# NIRGM_V6.net
KiCad netlist of a schematic drawn in EAGLE
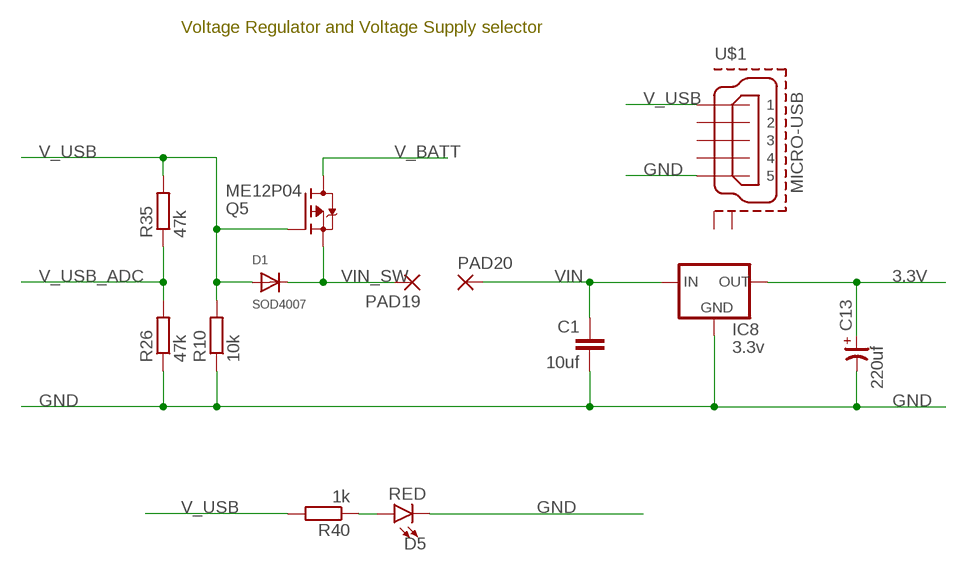
[diagram p0: schematic, sheet 1]
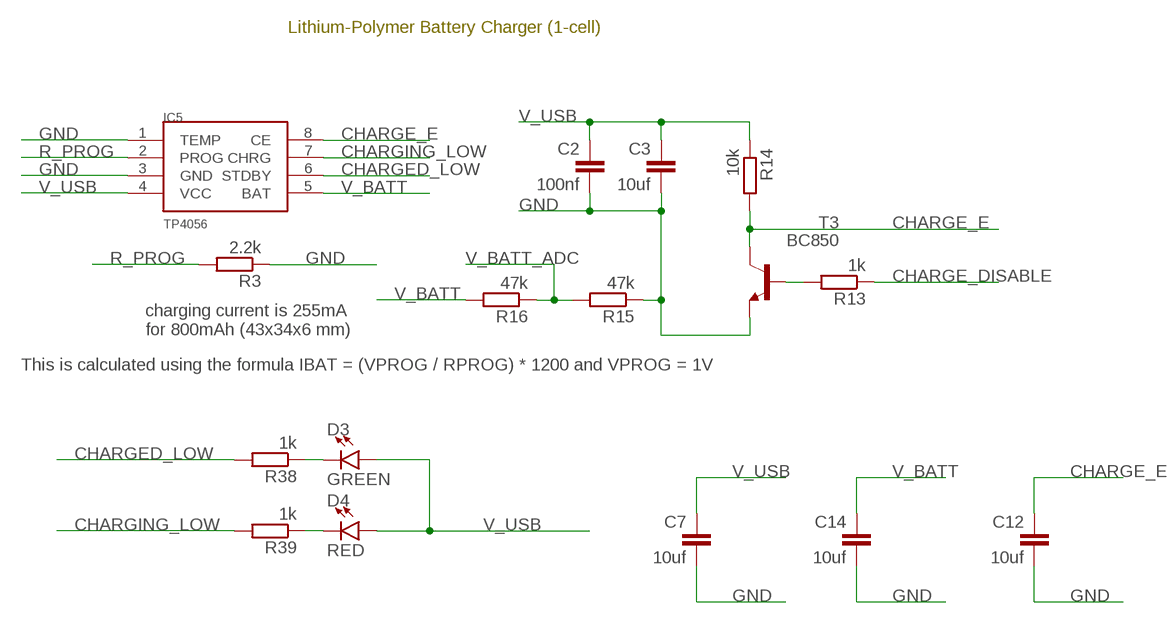
[diagram p1: schematic, sheet 2]
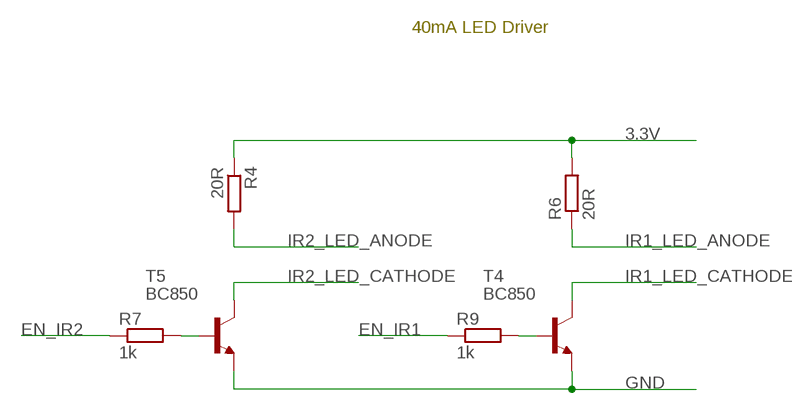
[diagram p2: schematic, sheet 3]
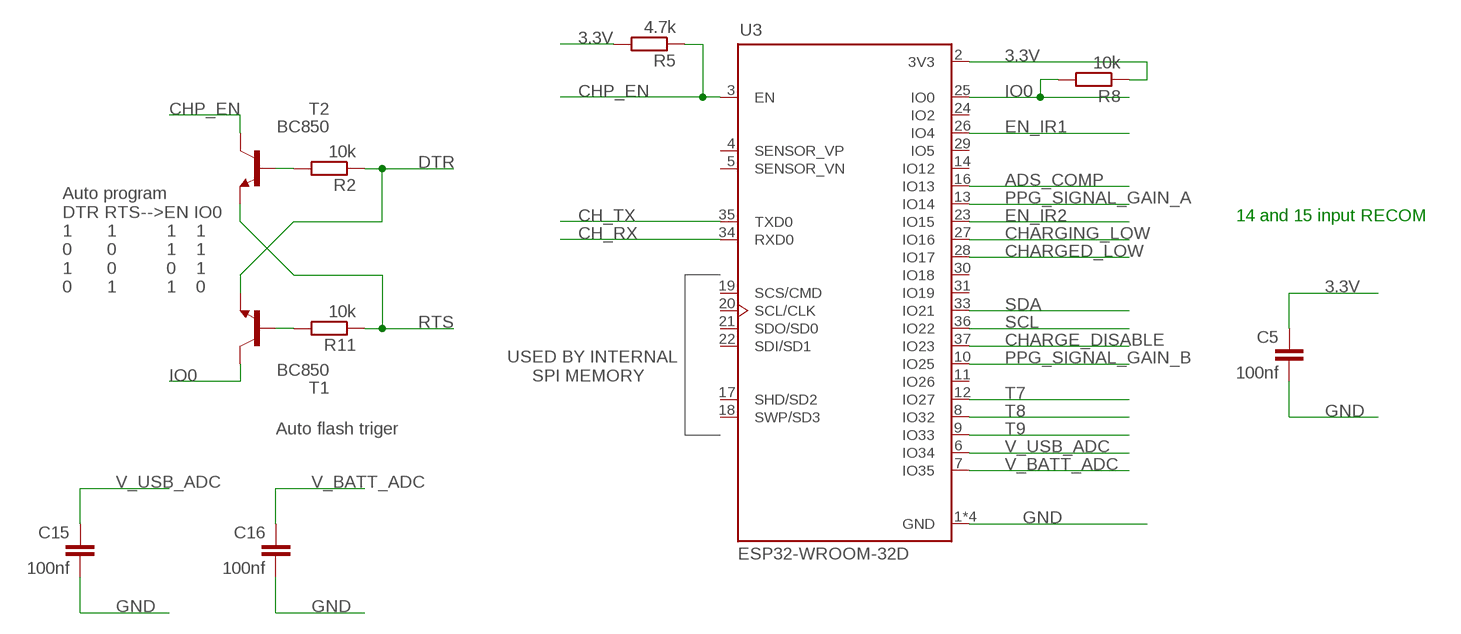
[diagram p3: schematic, sheet 4]
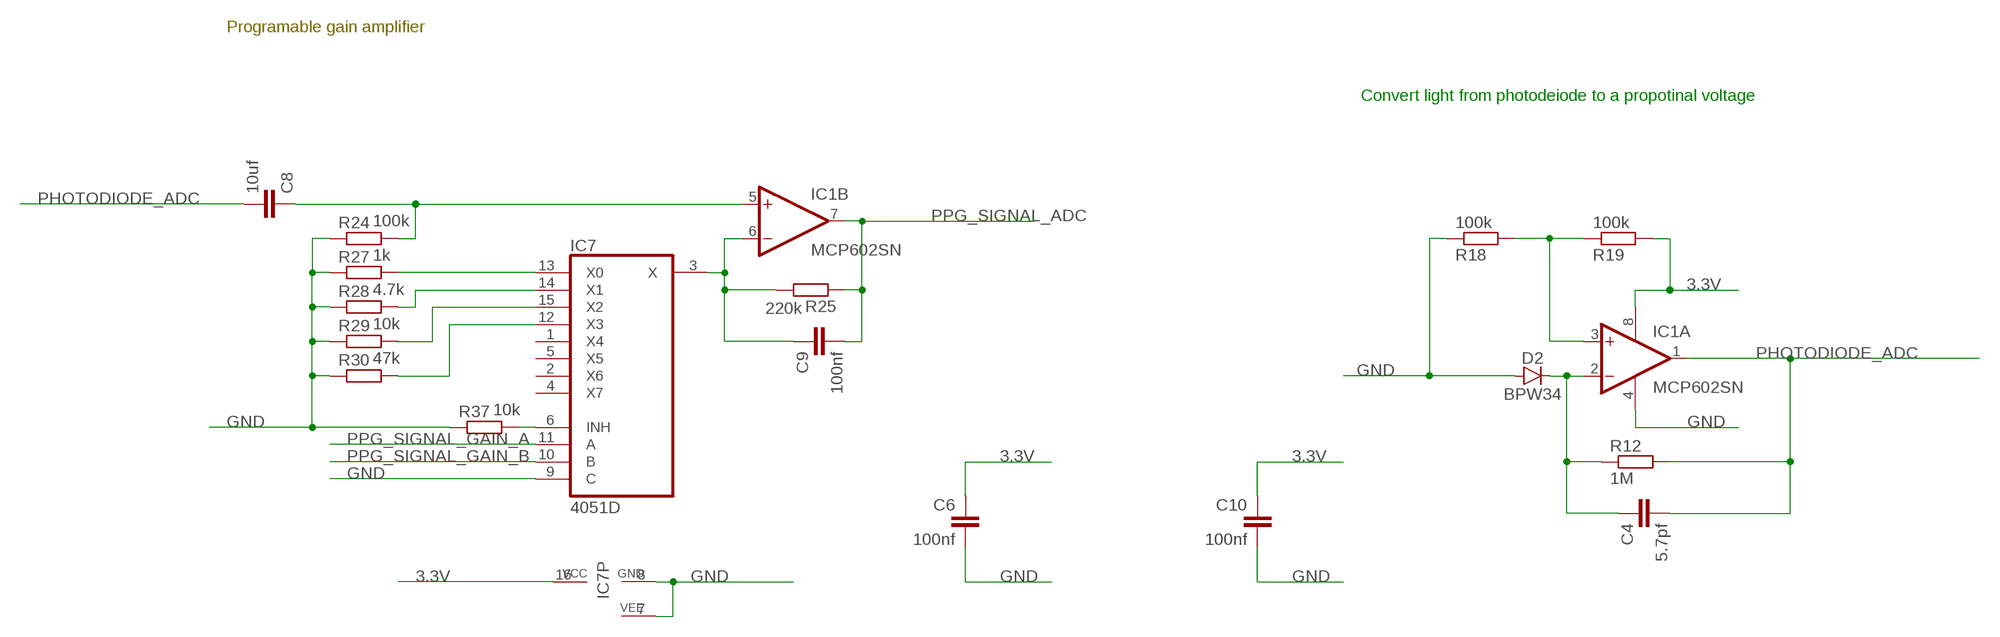
[diagram p4: schematic, sheet 5]
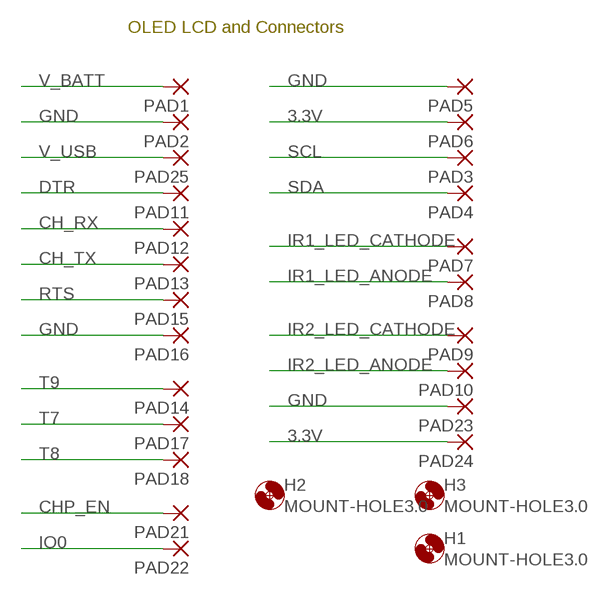
[diagram p5: schematic, sheet 6]
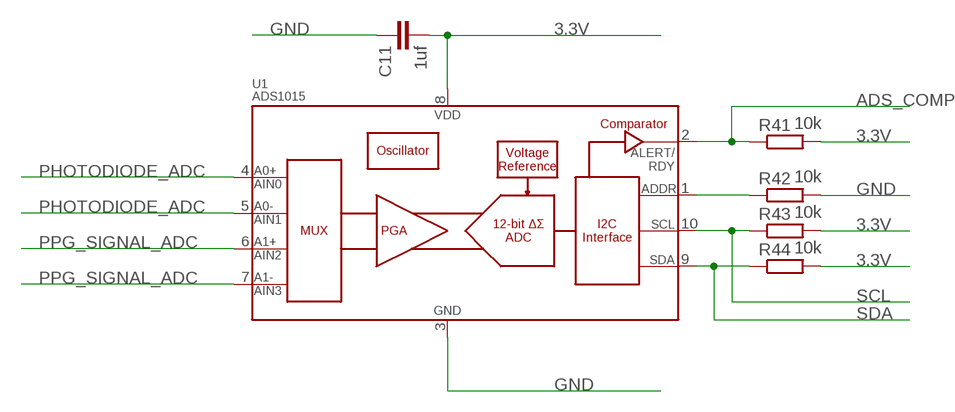
[diagram p6: schematic, sheet 7]

(export (version "E")
  (design (tool "Eeschema 10.0.6"))
  (components
    (comp (ref "C11")
      (value "1uf")
      (footprint "eagle-import:C1206K")
      (libsource (lib "eagle-import") (part "C-EUC1206K"))
    )
    (comp (ref "R41")
      (value "10k")
      (footprint "eagle-import:R1206")
      (libsource (lib "eagle-import") (part "R-EU_R1206"))
    )
    (comp (ref "R42")
      (value "10k")
      (footprint "eagle-import:R1206")
      (libsource (lib "eagle-import") (part "R-EU_R1206"))
    )
    (comp (ref "R43")
      (value "10k")
      (footprint "eagle-import:R1206")
      (libsource (lib "eagle-import") (part "R-EU_R1206"))
    )
    (comp (ref "R44")
      (value "10k")
      (footprint "eagle-import:R1206")
      (libsource (lib "eagle-import") (part "R-EU_R1206"))
    )
    (comp (ref "U1")
      (value "ADS1015")
      (footprint "eagle-import:MSOP10")
      (libsource (lib "eagle-import") (part "ADS1015"))
    )
    (comp (ref "C2")
      (value "100nf")
      (footprint "eagle-import:C1206K")
      (libsource (lib "eagle-import") (part "C-EUC1206K"))
    )
    (comp (ref "C3")
      (value "10uf")
      (footprint "eagle-import:C1206K")
      (libsource (lib "eagle-import") (part "C-EUC1206K"))
    )
    (comp (ref "C7")
      (value "10uf")
      (footprint "eagle-import:C1206K")
      (libsource (lib "eagle-import") (part "C-EUC1206K"))
    )
    (comp (ref "C12")
      (value "10uf")
      (footprint "eagle-import:C1206K")
      (libsource (lib "eagle-import") (part "C-EUC1206K"))
    )
    (comp (ref "C14")
      (value "10uf")
      (footprint "eagle-import:C1206K")
      (libsource (lib "eagle-import") (part "C-EUC1206K"))
    )
    (comp (ref "D3")
      (value "GREEN")
      (footprint "eagle-import:LED-1206")
      (libsource (lib "eagle-import") (part "LED-GREEN1206"))
    )
    (comp (ref "D4")
      (value "RED")
      (footprint "eagle-import:LED-1206")
      (libsource (lib "eagle-import") (part "LED-GREEN1206"))
    )
    (comp (ref "IC5")
      (value "TP4056")
      (footprint "eagle-import:SOP-8")
      (libsource (lib "eagle-import") (part "TP4056"))
    )
    (comp (ref "R3")
      (value "2.2k")
      (footprint "eagle-import:R1206")
      (libsource (lib "eagle-import") (part "R-EU_R1206"))
    )
    (comp (ref "R13")
      (value "1k")
      (footprint "eagle-import:R1206")
      (libsource (lib "eagle-import") (part "R-EU_R1206"))
    )
    (comp (ref "R14")
      (value "10k")
      (footprint "eagle-import:R1206")
      (libsource (lib "eagle-import") (part "R-EU_R1206"))
    )
    (comp (ref "R15")
      (value "47k")
      (footprint "eagle-import:R1206")
      (libsource (lib "eagle-import") (part "R-EU_R1206"))
    )
    (comp (ref "R16")
      (value "47k")
      (footprint "eagle-import:R1206")
      (libsource (lib "eagle-import") (part "R-EU_R1206"))
    )
    (comp (ref "R38")
      (value "1k")
      (footprint "eagle-import:R1206")
      (libsource (lib "eagle-import") (part "R-EU_R1206"))
    )
    (comp (ref "R39")
      (value "1k")
      (footprint "eagle-import:R1206")
      (libsource (lib "eagle-import") (part "R-EU_R1206"))
    )
    (comp (ref "T3")
      (value "BC850")
      (footprint "eagle-import:SOT23")
      (libsource (lib "eagle-import") (part "BC850"))
    )
    (comp (ref "C1")
      (value "10uf")
      (footprint "eagle-import:C1206K")
      (libsource (lib "eagle-import") (part "C-EUC1206K"))
    )
    (comp (ref "C13")
      (value "220uf")
      (footprint "eagle-import:7343_T")
      (libsource (lib "eagle-import") (part "CP-7343"))
    )
    (comp (ref "D1")
      (value "SOD4007")
      (footprint "eagle-import:SOD-123FL")
      (libsource (lib "eagle-import") (part "DIODE_SOD-123FL"))
    )
    (comp (ref "D5")
      (value "RED")
      (footprint "eagle-import:LED-1206")
      (libsource (lib "eagle-import") (part "LED-GREEN1206"))
    )
    (comp (ref "IC8")
      (value "3.3v")
      (footprint "eagle-import:TO252")
      (libsource (lib "eagle-import") (part "LM1117TO252"))
    )
    (comp (ref "PAD19")
      (value "SMD2")
      (footprint "eagle-import:SMD1,27-2,54")
      (libsource (lib "eagle-import") (part "SMD2"))
    )
    (comp (ref "PAD20")
      (value "SMD2")
      (footprint "eagle-import:SMD1,27-2,54")
      (libsource (lib "eagle-import") (part "SMD2"))
    )
    (comp (ref "Q5")
      (value "ME12P04")
      (footprint "eagle-import:TO252")
      (libsource (lib "eagle-import") (part "FDD4141TO252"))
    )
    (comp (ref "R10")
      (value "10k")
      (footprint "eagle-import:R1206")
      (libsource (lib "eagle-import") (part "R-EU_R1206"))
    )
    (comp (ref "R26")
      (value "47k")
      (footprint "eagle-import:R1206")
      (libsource (lib "eagle-import") (part "R-EU_R1206"))
    )
    (comp (ref "R35")
      (value "47k")
      (footprint "eagle-import:R1206")
      (libsource (lib "eagle-import") (part "R-EU_R1206"))
    )
    (comp (ref "R40")
      (value "1k")
      (footprint "eagle-import:R1206")
      (libsource (lib "eagle-import") (part "R-EU_R1206"))
    )
    (comp (ref "U$1")
      (value "MICRO-USB")
      (footprint "eagle-import:47589-0001")
      (libsource (lib "eagle-import") (part "MICRO-USB-RECEPTACLE47589-0001"))
    )
    (comp (ref "H1")
      (value "MOUNT-HOLE3.0")
      (footprint "eagle-import:3,0")
      (libsource (lib "eagle-import") (part "MOUNT-HOLE3.0"))
    )
    (comp (ref "H2")
      (value "MOUNT-HOLE3.0")
      (footprint "eagle-import:3,0")
      (libsource (lib "eagle-import") (part "MOUNT-HOLE3.0"))
    )
    (comp (ref "H3")
      (value "MOUNT-HOLE3.0")
      (footprint "eagle-import:3,0")
      (libsource (lib "eagle-import") (part "MOUNT-HOLE3.0"))
    )
    (comp (ref "PAD1")
      (value "WIREPADSMD5-2,5")
      (footprint "eagle-import:5-2,5")
      (libsource (lib "eagle-import") (part "WIREPADSMD5-2,5"))
    )
    (comp (ref "PAD2")
      (value "WIREPADSMD5-2,5")
      (footprint "eagle-import:5-2,5")
      (libsource (lib "eagle-import") (part "WIREPADSMD5-2,5"))
    )
    (comp (ref "PAD3")
      (value "SMD2")
      (footprint "eagle-import:SMD1,27-2,54")
      (libsource (lib "eagle-import") (part "SMD2"))
    )
    (comp (ref "PAD4")
      (value "SMD2")
      (footprint "eagle-import:SMD1,27-2,54")
      (libsource (lib "eagle-import") (part "SMD2"))
    )
    (comp (ref "PAD5")
      (value "SMD2")
      (footprint "eagle-import:SMD1,27-2,54")
      (libsource (lib "eagle-import") (part "SMD2"))
    )
    (comp (ref "PAD6")
      (value "SMD2")
      (footprint "eagle-import:SMD1,27-2,54")
      (libsource (lib "eagle-import") (part "SMD2"))
    )
    (comp (ref "PAD7")
      (value "SMD2")
      (footprint "eagle-import:SMD1,27-2,54")
      (libsource (lib "eagle-import") (part "SMD2"))
    )
    (comp (ref "PAD8")
      (value "SMD2")
      (footprint "eagle-import:SMD1,27-2,54")
      (libsource (lib "eagle-import") (part "SMD2"))
    )
    (comp (ref "PAD9")
      (value "SMD2")
      (footprint "eagle-import:SMD1,27-2,54")
      (libsource (lib "eagle-import") (part "SMD2"))
    )
    (comp (ref "PAD10")
      (value "SMD2")
      (footprint "eagle-import:SMD1,27-2,54")
      (libsource (lib "eagle-import") (part "SMD2"))
    )
    (comp (ref "PAD11")
      (value "SMD2")
      (footprint "eagle-import:SMD1,27-2,54")
      (libsource (lib "eagle-import") (part "SMD2"))
    )
    (comp (ref "PAD12")
      (value "SMD2")
      (footprint "eagle-import:SMD1,27-2,54")
      (libsource (lib "eagle-import") (part "SMD2"))
    )
    (comp (ref "PAD13")
      (value "SMD2")
      (footprint "eagle-import:SMD1,27-2,54")
      (libsource (lib "eagle-import") (part "SMD2"))
    )
    (comp (ref "PAD14")
      (value "SMD2")
      (footprint "eagle-import:SMD1,27-2,54")
      (libsource (lib "eagle-import") (part "SMD2"))
    )
    (comp (ref "PAD15")
      (value "SMD2")
      (footprint "eagle-import:SMD1,27-2,54")
      (libsource (lib "eagle-import") (part "SMD2"))
    )
    (comp (ref "PAD16")
      (value "SMD2")
      (footprint "eagle-import:SMD1,27-2,54")
      (libsource (lib "eagle-import") (part "SMD2"))
    )
    (comp (ref "PAD17")
      (value "SMD2")
      (footprint "eagle-import:SMD1,27-2,54")
      (libsource (lib "eagle-import") (part "SMD2"))
    )
    (comp (ref "PAD18")
      (value "SMD2")
      (footprint "eagle-import:SMD1,27-2,54")
      (libsource (lib "eagle-import") (part "SMD2"))
    )
    (comp (ref "PAD21")
      (value "SMD2")
      (footprint "eagle-import:SMD1,27-2,54")
      (libsource (lib "eagle-import") (part "SMD2"))
    )
    (comp (ref "PAD22")
      (value "SMD2")
      (footprint "eagle-import:SMD1,27-2,54")
      (libsource (lib "eagle-import") (part "SMD2"))
    )
    (comp (ref "PAD23")
      (value "SMD2")
      (footprint "eagle-import:SMD1,27-2,54")
      (libsource (lib "eagle-import") (part "SMD2"))
    )
    (comp (ref "PAD24")
      (value "SMD2")
      (footprint "eagle-import:SMD1,27-2,54")
      (libsource (lib "eagle-import") (part "SMD2"))
    )
    (comp (ref "PAD25")
      (value "SMD2")
      (footprint "eagle-import:SMD1,27-2,54")
      (libsource (lib "eagle-import") (part "SMD2"))
    )
    (comp (ref "R4")
      (value "20R")
      (footprint "eagle-import:R1206")
      (libsource (lib "eagle-import") (part "R-EU_R1206"))
    )
    (comp (ref "R6")
      (value "20R")
      (footprint "eagle-import:R1206")
      (libsource (lib "eagle-import") (part "R-EU_R1206"))
    )
    (comp (ref "R7")
      (value "1k")
      (footprint "eagle-import:R1206")
      (libsource (lib "eagle-import") (part "R-EU_R1206"))
    )
    (comp (ref "R9")
      (value "1k")
      (footprint "eagle-import:R1206")
      (libsource (lib "eagle-import") (part "R-EU_R1206"))
    )
    (comp (ref "T4")
      (value "BC850")
      (footprint "eagle-import:SOT23")
      (libsource (lib "eagle-import") (part "BC850"))
    )
    (comp (ref "T5")
      (value "BC850")
      (footprint "eagle-import:SOT23")
      (libsource (lib "eagle-import") (part "BC850"))
    )
    (comp (ref "C5")
      (value "100nf")
      (footprint "eagle-import:C1206K")
      (libsource (lib "eagle-import") (part "C-EUC1206K"))
    )
    (comp (ref "C15")
      (value "100nf")
      (footprint "eagle-import:C1206K")
      (libsource (lib "eagle-import") (part "C-EUC1206K"))
    )
    (comp (ref "C16")
      (value "100nf")
      (footprint "eagle-import:C1206K")
      (libsource (lib "eagle-import") (part "C-EUC1206K"))
    )
    (comp (ref "R2")
      (value "10k")
      (footprint "eagle-import:R1206")
      (libsource (lib "eagle-import") (part "R-EU_R1206"))
    )
    (comp (ref "R5")
      (value "4.7k")
      (footprint "eagle-import:R1206")
      (libsource (lib "eagle-import") (part "R-EU_R1206"))
    )
    (comp (ref "R8")
      (value "10k")
      (footprint "eagle-import:R1206")
      (libsource (lib "eagle-import") (part "R-EU_R1206"))
    )
    (comp (ref "R11")
      (value "10k")
      (footprint "eagle-import:R1206")
      (libsource (lib "eagle-import") (part "R-EU_R1206"))
    )
    (comp (ref "T1")
      (value "BC850")
      (footprint "eagle-import:SOT23")
      (libsource (lib "eagle-import") (part "BC850"))
    )
    (comp (ref "T2")
      (value "BC850")
      (footprint "eagle-import:SOT23")
      (libsource (lib "eagle-import") (part "BC850"))
    )
    (comp (ref "U3")
      (value "ESP32-WROOM-32D")
      (footprint "eagle-import:MODULE_ESP32-WROOM-32D")
      (fields (field (name "MF") "Espressif Systems"))
      (libsource (lib "eagle-import") (part "ESP32-WROOM-32D"))
    )
    (comp (ref "C4")
      (value "5.7pf")
      (footprint "eagle-import:C1206K")
      (libsource (lib "eagle-import") (part "C-EUC1206K"))
    )
    (comp (ref "C6")
      (value "100nf")
      (footprint "eagle-import:C1206K")
      (libsource (lib "eagle-import") (part "C-EUC1206K"))
    )
    (comp (ref "C8")
      (value "10uf")
      (footprint "eagle-import:C1206K")
      (libsource (lib "eagle-import") (part "C-EUC1206K"))
    )
    (comp (ref "C9")
      (value "100nf")
      (footprint "eagle-import:C1206K")
      (libsource (lib "eagle-import") (part "C-EUC1206K"))
    )
    (comp (ref "C10")
      (value "100nf")
      (footprint "eagle-import:C1206K")
      (libsource (lib "eagle-import") (part "C-EUC1206K"))
    )
    (comp (ref "D2")
      (value "BPW34")
      (footprint "eagle-import:BPW34")
      (libsource (lib "eagle-import") (part "BPW34"))
    )
    (comp (ref "IC1")
      (value "MCP602SN")
      (footprint "eagle-import:SO08")
      (libsource (lib "eagle-import") (part "MCP602SN"))
    )
    (comp (ref "IC7")
      (value "4051D")
      (footprint "eagle-import:SO16")
      (libsource (lib "eagle-import") (part "4051D"))
    )
    (comp (ref "R12")
      (value "1M")
      (footprint "eagle-import:R1206")
      (libsource (lib "eagle-import") (part "R-EU_R1206"))
    )
    (comp (ref "R18")
      (value "100k")
      (footprint "eagle-import:R1206")
      (libsource (lib "eagle-import") (part "R-EU_R1206"))
    )
    (comp (ref "R19")
      (value "100k")
      (footprint "eagle-import:R1206")
      (libsource (lib "eagle-import") (part "R-EU_R1206"))
    )
    (comp (ref "R24")
      (value "100k")
      (footprint "eagle-import:R1206")
      (libsource (lib "eagle-import") (part "R-EU_R1206"))
    )
    (comp (ref "R25")
      (value "220k")
      (footprint "eagle-import:R1206")
      (libsource (lib "eagle-import") (part "R-EU_R1206"))
    )
    (comp (ref "R27")
      (value "1k")
      (footprint "eagle-import:R1206")
      (libsource (lib "eagle-import") (part "R-EU_R1206"))
    )
    (comp (ref "R28")
      (value "4.7k")
      (footprint "eagle-import:R1206")
      (libsource (lib "eagle-import") (part "R-EU_R1206"))
    )
    (comp (ref "R29")
      (value "10k")
      (footprint "eagle-import:R1206")
      (libsource (lib "eagle-import") (part "R-EU_R1206"))
    )
    (comp (ref "R30")
      (value "47k")
      (footprint "eagle-import:R1206")
      (libsource (lib "eagle-import") (part "R-EU_R1206"))
    )
    (comp (ref "R37")
      (value "10k")
      (footprint "eagle-import:R1206")
      (libsource (lib "eagle-import") (part "R-EU_R1206"))
    )
  )
  (nets
    (net (code "1") (name "3.3V") (class "Default")
      (node (ref "C10") (pin "1") (pinfunction "1_1") (pintype "passive"))
      (node (ref "C11") (pin "2") (pinfunction "2_2") (pintype "passive"))
      (node (ref "C13") (pin "+") (pinfunction "+_+") (pintype "passive"))
      (node (ref "C5") (pin "1") (pinfunction "1_1") (pintype "passive"))
      (node (ref "C6") (pin "1") (pinfunction "1_1") (pintype "passive"))
      (node (ref "IC1") (pin "8") (pinfunction "V+_8") (pintype "power_in"))
      (node (ref "IC7") (pin "16") (pinfunction "VCC_16") (pintype "power_in"))
      (node (ref "IC8") (pin "3") (pinfunction "OUT_3") (pintype "passive"))
      (node (ref "PAD24") (pin "1") (pinfunction "P_1") (pintype "passive"))
      (node (ref "PAD6") (pin "1") (pinfunction "P_1") (pintype "passive"))
      (node (ref "R19") (pin "2") (pinfunction "2_2") (pintype "passive"))
      (node (ref "R4") (pin "1") (pinfunction "1_1") (pintype "passive"))
      (node (ref "R41") (pin "2") (pinfunction "2_2") (pintype "passive"))
      (node (ref "R43") (pin "2") (pinfunction "2_2") (pintype "passive"))
      (node (ref "R44") (pin "2") (pinfunction "2_2") (pintype "passive"))
      (node (ref "R5") (pin "2") (pinfunction "2_2") (pintype "passive"))
      (node (ref "R6") (pin "2") (pinfunction "2_2") (pintype "passive"))
      (node (ref "R8") (pin "1") (pinfunction "1_1") (pintype "passive"))
      (node (ref "U1") (pin "8") (pinfunction "VDD_8") (pintype "bidirectional"))
      (node (ref "U3") (pin "2") (pinfunction "3V3_2") (pintype "power_in"))
    )
    (net (code "2") (name "ADS_COMP") (class "Default")
      (node (ref "R41") (pin "1") (pinfunction "1_1") (pintype "passive"))
      (node (ref "U1") (pin "2") (pinfunction "ALERT/RDY_2") (pintype "bidirectional"))
      (node (ref "U3") (pin "16") (pinfunction "IO13_16") (pintype "bidirectional"))
    )
    (net (code "3") (name "CHARGED_LOW") (class "Default")
      (node (ref "IC5") (pin "6") (pinfunction "STDBY_6") (pintype "bidirectional"))
      (node (ref "R38") (pin "2") (pinfunction "2_2") (pintype "passive"))
      (node (ref "U3") (pin "28") (pinfunction "IO17_28") (pintype "bidirectional"))
    )
    (net (code "4") (name "CHARGE_DISABLE") (class "Default")
      (node (ref "R13") (pin "1") (pinfunction "1_1") (pintype "passive"))
      (node (ref "U3") (pin "37") (pinfunction "IO23_37") (pintype "bidirectional"))
    )
    (net (code "5") (name "CHARGE_E") (class "Default")
      (node (ref "C12") (pin "1") (pinfunction "1_1") (pintype "passive"))
      (node (ref "IC5") (pin "8") (pinfunction "CE_8") (pintype "bidirectional"))
      (node (ref "R14") (pin "2") (pinfunction "2_2") (pintype "passive"))
      (node (ref "T3") (pin "3") (pinfunction "C_3") (pintype "passive"))
    )
    (net (code "6") (name "CHARGING_LOW") (class "Default")
      (node (ref "IC5") (pin "7") (pinfunction "CHRG_7") (pintype "bidirectional"))
      (node (ref "R39") (pin "2") (pinfunction "2_2") (pintype "passive"))
      (node (ref "U3") (pin "27") (pinfunction "IO16_27") (pintype "bidirectional"))
    )
    (net (code "7") (name "CHP_EN") (class "Default")
      (node (ref "PAD21") (pin "1") (pinfunction "P_1") (pintype "passive"))
      (node (ref "R5") (pin "1") (pinfunction "1_1") (pintype "passive"))
      (node (ref "T2") (pin "3") (pinfunction "C_3") (pintype "passive"))
      (node (ref "U3") (pin "3") (pinfunction "EN_3") (pintype "input"))
    )
    (net (code "8") (name "CH_RX") (class "Default")
      (node (ref "PAD12") (pin "1") (pinfunction "P_1") (pintype "passive"))
      (node (ref "U3") (pin "34") (pinfunction "RXD0_34") (pintype "bidirectional"))
    )
    (net (code "9") (name "CH_TX") (class "Default")
      (node (ref "PAD13") (pin "1") (pinfunction "P_1") (pintype "passive"))
      (node (ref "U3") (pin "35") (pinfunction "TXD0_35") (pintype "bidirectional"))
    )
    (net (code "10") (name "DTR") (class "Default")
      (node (ref "PAD11") (pin "1") (pinfunction "P_1") (pintype "passive"))
      (node (ref "R2") (pin "1") (pinfunction "1_1") (pintype "passive"))
      (node (ref "T1") (pin "2") (pinfunction "E_2") (pintype "passive"))
    )
    (net (code "11") (name "EN_IR1") (class "Default")
      (node (ref "R9") (pin "1") (pinfunction "1_1") (pintype "passive"))
      (node (ref "U3") (pin "26") (pinfunction "IO4_26") (pintype "bidirectional"))
    )
    (net (code "12") (name "EN_IR2") (class "Default")
      (node (ref "R7") (pin "1") (pinfunction "1_1") (pintype "passive"))
      (node (ref "U3") (pin "23") (pinfunction "IO15_23") (pintype "bidirectional"))
    )
    (net (code "13") (name "GND") (class "Default")
      (node (ref "C1") (pin "2") (pinfunction "2_2") (pintype "passive"))
      (node (ref "C10") (pin "2") (pinfunction "2_2") (pintype "passive"))
      (node (ref "C11") (pin "1") (pinfunction "1_1") (pintype "passive"))
      (node (ref "C12") (pin "2") (pinfunction "2_2") (pintype "passive"))
      (node (ref "C13") (pin "-") (pinfunction "-_-") (pintype "passive"))
      (node (ref "C14") (pin "2") (pinfunction "2_2") (pintype "passive"))
      (node (ref "C15") (pin "2") (pinfunction "2_2") (pintype "passive"))
      (node (ref "C16") (pin "2") (pinfunction "2_2") (pintype "passive"))
      (node (ref "C2") (pin "2") (pinfunction "2_2") (pintype "passive"))
      (node (ref "C3") (pin "2") (pinfunction "2_2") (pintype "passive"))
      (node (ref "C5") (pin "2") (pinfunction "2_2") (pintype "passive"))
      (node (ref "C6") (pin "2") (pinfunction "2_2") (pintype "passive"))
      (node (ref "C7") (pin "2") (pinfunction "2_2") (pintype "passive"))
      (node (ref "D2") (pin "P$1") (pinfunction "A_P$1") (pintype "passive"))
      (node (ref "D5") (pin "C") (pinfunction "C_C") (pintype "passive"))
      (node (ref "IC1") (pin "4") (pinfunction "V-_4") (pintype "power_in"))
      (node (ref "IC5") (pin "1") (pinfunction "TEMP_1") (pintype "bidirectional"))
      (node (ref "IC5") (pin "3") (pinfunction "GND_3") (pintype "bidirectional"))
      (node (ref "IC7") (pin "7") (pinfunction "VEE_7") (pintype "power_in"))
      (node (ref "IC7") (pin "8") (pinfunction "GND_8") (pintype "power_in"))
      (node (ref "IC7") (pin "9") (pinfunction "C_9") (pintype "input"))
      (node (ref "IC8") (pin "1") (pinfunction "GND_1") (pintype "input"))
      (node (ref "PAD16") (pin "1") (pinfunction "P_1") (pintype "passive"))
      (node (ref "PAD2") (pin "1") (pinfunction "P_1") (pintype "passive"))
      (node (ref "PAD23") (pin "1") (pinfunction "P_1") (pintype "passive"))
      (node (ref "PAD5") (pin "1") (pinfunction "P_1") (pintype "passive"))
      (node (ref "R10") (pin "1") (pinfunction "1_1") (pintype "passive"))
      (node (ref "R15") (pin "1") (pinfunction "1_1") (pintype "passive"))
      (node (ref "R18") (pin "1") (pinfunction "1_1") (pintype "passive"))
      (node (ref "R24") (pin "1") (pinfunction "1_1") (pintype "passive"))
      (node (ref "R26") (pin "1") (pinfunction "1_1") (pintype "passive"))
      (node (ref "R27") (pin "1") (pinfunction "1_1") (pintype "passive"))
      (node (ref "R28") (pin "1") (pinfunction "1_1") (pintype "passive"))
      (node (ref "R29") (pin "1") (pinfunction "1_1") (pintype "passive"))
      (node (ref "R3") (pin "1") (pinfunction "1_1") (pintype "passive"))
      (node (ref "R30") (pin "1") (pinfunction "1_1") (pintype "passive"))
      (node (ref "R37") (pin "1") (pinfunction "1_1") (pintype "passive"))
      (node (ref "R42") (pin "2") (pinfunction "2_2") (pintype "passive"))
      (node (ref "T3") (pin "2") (pinfunction "E_2") (pintype "passive"))
      (node (ref "T4") (pin "2") (pinfunction "E_2") (pintype "passive"))
      (node (ref "T5") (pin "2") (pinfunction "E_2") (pintype "passive"))
      (node (ref "U$1") (pin "5") (pinfunction "5_5") (pintype "input"))
      (node (ref "U1") (pin "3") (pinfunction "VSS_3") (pintype "bidirectional"))
      (node (ref "U3") (pin "1") (pinfunction "GND_1") (pintype "power_in"))
      (node (ref "U3") (pin "15") (pinfunction "GND_15") (pintype "power_in"))
      (node (ref "U3") (pin "38") (pinfunction "GND_38") (pintype "power_in"))
      (node (ref "U3") (pin "39") (pinfunction "GND_39") (pintype "power_in"))
    )
    (net (code "14") (name "IO0") (class "Default")
      (node (ref "PAD22") (pin "1") (pinfunction "P_1") (pintype "passive"))
      (node (ref "R8") (pin "2") (pinfunction "2_2") (pintype "passive"))
      (node (ref "T1") (pin "3") (pinfunction "C_3") (pintype "passive"))
      (node (ref "U3") (pin "25") (pinfunction "IO0_25") (pintype "bidirectional"))
    )
    (net (code "15") (name "IR1_LED_ANODE") (class "Default")
      (node (ref "PAD8") (pin "1") (pinfunction "P_1") (pintype "passive"))
      (node (ref "R6") (pin "1") (pinfunction "1_1") (pintype "passive"))
    )
    (net (code "16") (name "IR1_LED_CATHODE") (class "Default")
      (node (ref "PAD7") (pin "1") (pinfunction "P_1") (pintype "passive"))
      (node (ref "T4") (pin "3") (pinfunction "C_3") (pintype "passive"))
    )
    (net (code "17") (name "IR2_LED_ANODE") (class "Default")
      (node (ref "PAD10") (pin "1") (pinfunction "P_1") (pintype "passive"))
      (node (ref "R4") (pin "2") (pinfunction "2_2") (pintype "passive"))
    )
    (net (code "18") (name "IR2_LED_CATHODE") (class "Default")
      (node (ref "PAD9") (pin "1") (pinfunction "P_1") (pintype "passive"))
      (node (ref "T5") (pin "3") (pinfunction "C_3") (pintype "passive"))
    )
    (net (code "19") (name "Net-(D2-C)") (class "Default")
      (node (ref "C4") (pin "1") (pinfunction "1_1") (pintype "passive"))
      (node (ref "D2") (pin "P$2") (pinfunction "C_P$2") (pintype "passive"))
      (node (ref "IC1") (pin "2") (pinfunction "-IN_2") (pintype "input"))
      (node (ref "R12") (pin "1") (pinfunction "1_1") (pintype "passive"))
    )
    (net (code "20") (name "Net-(D3-PadC)") (class "Default")
      (node (ref "D3") (pin "C") (pinfunction "C_C") (pintype "passive"))
      (node (ref "R38") (pin "1") (pinfunction "1_1") (pintype "passive"))
    )
    (net (code "21") (name "Net-(D4-PadC)") (class "Default")
      (node (ref "D4") (pin "C") (pinfunction "C_C") (pintype "passive"))
      (node (ref "R39") (pin "1") (pinfunction "1_1") (pintype "passive"))
    )
    (net (code "22") (name "Net-(D5-PadA)") (class "Default")
      (node (ref "D5") (pin "A") (pinfunction "A_A") (pintype "passive"))
      (node (ref "R40") (pin "1") (pinfunction "1_1") (pintype "passive"))
    )
    (net (code "23") (name "Net-(IC1A-+IN)") (class "Default")
      (node (ref "IC1") (pin "3") (pinfunction "+IN_3") (pintype "input"))
      (node (ref "R18") (pin "2") (pinfunction "2_2") (pintype "passive"))
      (node (ref "R19") (pin "1") (pinfunction "1_1") (pintype "passive"))
    )
    (net (code "24") (name "Net-(IC1B-+IN)") (class "Default")
      (node (ref "C8") (pin "1") (pinfunction "1_1") (pintype "passive"))
      (node (ref "IC1") (pin "5") (pinfunction "+IN_5") (pintype "input"))
      (node (ref "R24") (pin "2") (pinfunction "2_2") (pintype "passive"))
    )
    (net (code "25") (name "Net-(IC1B--IN)") (class "Default")
      (node (ref "C9") (pin "1") (pinfunction "1_1") (pintype "passive"))
      (node (ref "IC1") (pin "6") (pinfunction "-IN_6") (pintype "input"))
      (node (ref "IC7") (pin "3") (pinfunction "X_3") (pintype "bidirectional"))
      (node (ref "R25") (pin "2") (pinfunction "2_2") (pintype "passive"))
    )
    (net (code "26") (name "Net-(IC7A-INH)") (class "Default")
      (node (ref "IC7") (pin "6") (pinfunction "INH_6") (pintype "input"))
      (node (ref "R37") (pin "2") (pinfunction "2_2") (pintype "passive"))
    )
    (net (code "27") (name "Net-(IC7A-X0)") (class "Default")
      (node (ref "IC7") (pin "13") (pinfunction "X0_13") (pintype "bidirectional"))
      (node (ref "R27") (pin "2") (pinfunction "2_2") (pintype "passive"))
    )
    (net (code "28") (name "Net-(IC7A-X1)") (class "Default")
      (node (ref "IC7") (pin "14") (pinfunction "X1_14") (pintype "bidirectional"))
      (node (ref "R28") (pin "2") (pinfunction "2_2") (pintype "passive"))
    )
    (net (code "29") (name "Net-(IC7A-X2)") (class "Default")
      (node (ref "IC7") (pin "15") (pinfunction "X2_15") (pintype "bidirectional"))
      (node (ref "R29") (pin "2") (pinfunction "2_2") (pintype "passive"))
    )
    (net (code "30") (name "Net-(IC7A-X3)") (class "Default")
      (node (ref "IC7") (pin "12") (pinfunction "X3_12") (pintype "bidirectional"))
      (node (ref "R30") (pin "2") (pinfunction "2_2") (pintype "passive"))
    )
    (net (code "31") (name "Net-(T1-B)") (class "Default")
      (node (ref "R11") (pin "2") (pinfunction "2_2") (pintype "passive"))
      (node (ref "T1") (pin "1") (pinfunction "B_1") (pintype "passive"))
    )
    (net (code "32") (name "Net-(T2-B)") (class "Default")
      (node (ref "R2") (pin "2") (pinfunction "2_2") (pintype "passive"))
      (node (ref "T2") (pin "1") (pinfunction "B_1") (pintype "passive"))
    )
    (net (code "33") (name "Net-(T3-B)") (class "Default")
      (node (ref "R13") (pin "2") (pinfunction "2_2") (pintype "passive"))
      (node (ref "T3") (pin "1") (pinfunction "B_1") (pintype "passive"))
    )
    (net (code "34") (name "Net-(T4-B)") (class "Default")
      (node (ref "R9") (pin "2") (pinfunction "2_2") (pintype "passive"))
      (node (ref "T4") (pin "1") (pinfunction "B_1") (pintype "passive"))
    )
    (net (code "35") (name "Net-(T5-B)") (class "Default")
      (node (ref "R7") (pin "2") (pinfunction "2_2") (pintype "passive"))
      (node (ref "T5") (pin "1") (pinfunction "B_1") (pintype "passive"))
    )
    (net (code "36") (name "Net-(U1-ADDR)") (class "Default")
      (node (ref "R42") (pin "1") (pinfunction "1_1") (pintype "passive"))
      (node (ref "U1") (pin "1") (pinfunction "ADDR_1") (pintype "bidirectional"))
    )
    (net (code "37") (name "PHOTODIODE_ADC") (class "Default")
      (node (ref "C4") (pin "2") (pinfunction "2_2") (pintype "passive"))
      (node (ref "C8") (pin "2") (pinfunction "2_2") (pintype "passive"))
      (node (ref "IC1") (pin "1") (pinfunction "OUT_1") (pintype "output"))
      (node (ref "R12") (pin "2") (pinfunction "2_2") (pintype "passive"))
      (node (ref "U1") (pin "4") (pinfunction "AIN0_4") (pintype "bidirectional"))
      (node (ref "U1") (pin "5") (pinfunction "AIN1_5") (pintype "bidirectional"))
    )
    (net (code "38") (name "PPG_SIGNAL_ADC") (class "Default")
      (node (ref "C9") (pin "2") (pinfunction "2_2") (pintype "passive"))
      (node (ref "IC1") (pin "7") (pinfunction "OUT_7") (pintype "output"))
      (node (ref "R25") (pin "1") (pinfunction "1_1") (pintype "passive"))
      (node (ref "U1") (pin "6") (pinfunction "AIN2_6") (pintype "bidirectional"))
      (node (ref "U1") (pin "7") (pinfunction "AIN3_7") (pintype "bidirectional"))
    )
    (net (code "39") (name "PPG_SIGNAL_GAIN_A") (class "Default")
      (node (ref "IC7") (pin "11") (pinfunction "A_11") (pintype "input"))
      (node (ref "U3") (pin "13") (pinfunction "IO14_13") (pintype "bidirectional"))
    )
    (net (code "40") (name "PPG_SIGNAL_GAIN_B") (class "Default")
      (node (ref "IC7") (pin "10") (pinfunction "B_10") (pintype "input"))
      (node (ref "U3") (pin "10") (pinfunction "IO25_10") (pintype "bidirectional"))
    )
    (net (code "41") (name "RTS") (class "Default")
      (node (ref "PAD15") (pin "1") (pinfunction "P_1") (pintype "passive"))
      (node (ref "R11") (pin "1") (pinfunction "1_1") (pintype "passive"))
      (node (ref "T2") (pin "2") (pinfunction "E_2") (pintype "passive"))
    )
    (net (code "42") (name "R_PROG") (class "Default")
      (node (ref "IC5") (pin "2") (pinfunction "PROG_2") (pintype "bidirectional"))
      (node (ref "R3") (pin "2") (pinfunction "2_2") (pintype "passive"))
    )
    (net (code "43") (name "SCL") (class "Default")
      (node (ref "PAD3") (pin "1") (pinfunction "P_1") (pintype "passive"))
      (node (ref "R43") (pin "1") (pinfunction "1_1") (pintype "passive"))
      (node (ref "U1") (pin "10") (pinfunction "SCL_10") (pintype "bidirectional"))
      (node (ref "U3") (pin "36") (pinfunction "IO22_36") (pintype "bidirectional"))
    )
    (net (code "44") (name "SDA") (class "Default")
      (node (ref "PAD4") (pin "1") (pinfunction "P_1") (pintype "passive"))
      (node (ref "R44") (pin "1") (pinfunction "1_1") (pintype "passive"))
      (node (ref "U1") (pin "9") (pinfunction "SDA_9") (pintype "bidirectional"))
      (node (ref "U3") (pin "33") (pinfunction "IO21_33") (pintype "bidirectional"))
    )
    (net (code "45") (name "T7") (class "Default")
      (node (ref "PAD17") (pin "1") (pinfunction "P_1") (pintype "passive"))
      (node (ref "U3") (pin "12") (pinfunction "IO27_12") (pintype "bidirectional"))
    )
    (net (code "46") (name "T8") (class "Default")
      (node (ref "PAD18") (pin "1") (pinfunction "P_1") (pintype "passive"))
      (node (ref "U3") (pin "8") (pinfunction "IO32_8") (pintype "bidirectional"))
    )
    (net (code "47") (name "T9") (class "Default")
      (node (ref "PAD14") (pin "1") (pinfunction "P_1") (pintype "passive"))
      (node (ref "U3") (pin "9") (pinfunction "IO33_9") (pintype "bidirectional"))
    )
    (net (code "48") (name "VIN") (class "Default")
      (node (ref "C1") (pin "1") (pinfunction "1_1") (pintype "passive"))
      (node (ref "IC8") (pin "2") (pinfunction "IN_2") (pintype "input"))
      (node (ref "PAD20") (pin "1") (pinfunction "P_1") (pintype "passive"))
    )
    (net (code "49") (name "VIN_SW") (class "Default")
      (node (ref "D1") (pin "C") (pinfunction "C_C") (pintype "passive"))
      (node (ref "PAD19") (pin "1") (pinfunction "P_1") (pintype "passive"))
      (node (ref "Q5") (pin "2") (pinfunction "S_2") (pintype "passive"))
    )
    (net (code "50") (name "V_BATT") (class "Default")
      (node (ref "C14") (pin "1") (pinfunction "1_1") (pintype "passive"))
      (node (ref "IC5") (pin "5") (pinfunction "BAT_5") (pintype "bidirectional"))
      (node (ref "PAD1") (pin "1") (pinfunction "P_1") (pintype "passive"))
      (node (ref "Q5") (pin "3") (pinfunction "D_3") (pintype "passive"))
      (node (ref "R16") (pin "2") (pinfunction "2_2") (pintype "passive"))
    )
    (net (code "51") (name "V_BATT_ADC") (class "Default")
      (node (ref "C16") (pin "1") (pinfunction "1_1") (pintype "passive"))
      (node (ref "R15") (pin "2") (pinfunction "2_2") (pintype "passive"))
      (node (ref "R16") (pin "1") (pinfunction "1_1") (pintype "passive"))
      (node (ref "U3") (pin "7") (pinfunction "IO35_7") (pintype "bidirectional"))
    )
    (net (code "52") (name "V_USB") (class "Default")
      (node (ref "C2") (pin "1") (pinfunction "1_1") (pintype "passive"))
      (node (ref "C3") (pin "1") (pinfunction "1_1") (pintype "passive"))
      (node (ref "C7") (pin "1") (pinfunction "1_1") (pintype "passive"))
      (node (ref "D1") (pin "A") (pinfunction "A_A") (pintype "passive"))
      (node (ref "D3") (pin "A") (pinfunction "A_A") (pintype "passive"))
      (node (ref "D4") (pin "A") (pinfunction "A_A") (pintype "passive"))
      (node (ref "IC5") (pin "4") (pinfunction "VCC_4") (pintype "bidirectional"))
      (node (ref "PAD25") (pin "1") (pinfunction "P_1") (pintype "passive"))
      (node (ref "Q5") (pin "1") (pinfunction "G_1") (pintype "passive"))
      (node (ref "R10") (pin "2") (pinfunction "2_2") (pintype "passive"))
      (node (ref "R14") (pin "1") (pinfunction "1_1") (pintype "passive"))
      (node (ref "R35") (pin "2") (pinfunction "2_2") (pintype "passive"))
      (node (ref "R40") (pin "2") (pinfunction "2_2") (pintype "passive"))
      (node (ref "U$1") (pin "1") (pinfunction "1_1") (pintype "input"))
    )
    (net (code "53") (name "V_USB_ADC") (class "Default")
      (node (ref "C15") (pin "1") (pinfunction "1_1") (pintype "passive"))
      (node (ref "R26") (pin "2") (pinfunction "2_2") (pintype "passive"))
      (node (ref "R35") (pin "1") (pinfunction "1_1") (pintype "passive"))
      (node (ref "U3") (pin "6") (pinfunction "IO34_6") (pintype "bidirectional"))
    )
    (net (code "54") (name "unconnected-(IC7A-X4-Pad1)") (class "Default")
      (node (ref "IC7") (pin "1") (pinfunction "X4_1") (pintype "bidirectional"))
    )
    (net (code "55") (name "unconnected-(IC7A-X5-Pad5)") (class "Default")
      (node (ref "IC7") (pin "5") (pinfunction "X5_5") (pintype "bidirectional"))
    )
    (net (code "56") (name "unconnected-(IC7A-X6-Pad2)") (class "Default")
      (node (ref "IC7") (pin "2") (pinfunction "X6_2") (pintype "bidirectional"))
    )
    (net (code "57") (name "unconnected-(IC7A-X7-Pad4)") (class "Default")
      (node (ref "IC7") (pin "4") (pinfunction "X7_4") (pintype "bidirectional"))
    )
    (net (code "58") (name "unconnected-(U$1-GND1-PadP$1)") (class "Default")
      (node (ref "U$1") (pin "P$1") (pinfunction "GND1_P$1") (pintype "bidirectional"))
    )
    (net (code "59") (name "unconnected-(U$1-GND2-PadP$2)") (class "Default")
      (node (ref "U$1") (pin "P$2") (pinfunction "GND2_P$2") (pintype "bidirectional"))
    )
    (net (code "60") (name "unconnected-(U$1-Pad2)") (class "Default")
      (node (ref "U$1") (pin "2") (pinfunction "2_2") (pintype "input"))
    )
    (net (code "61") (name "unconnected-(U$1-Pad3)") (class "Default")
      (node (ref "U$1") (pin "3") (pinfunction "3_3") (pintype "input"))
    )
    (net (code "62") (name "unconnected-(U$1-Pad4)") (class "Default")
      (node (ref "U$1") (pin "4") (pinfunction "4_4") (pintype "input"))
    )
    (net (code "63") (name "unconnected-(U3-IO2-Pad24)") (class "Default")
      (node (ref "U3") (pin "24") (pinfunction "IO2_24") (pintype "bidirectional"))
    )
    (net (code "64") (name "unconnected-(U3-IO5-Pad29)") (class "Default")
      (node (ref "U3") (pin "29") (pinfunction "IO5_29") (pintype "bidirectional"))
    )
    (net (code "65") (name "unconnected-(U3-IO12-Pad14)") (class "Default")
      (node (ref "U3") (pin "14") (pinfunction "IO12_14") (pintype "bidirectional"))
    )
    (net (code "66") (name "unconnected-(U3-IO18-Pad30)") (class "Default")
      (node (ref "U3") (pin "30") (pinfunction "IO18_30") (pintype "bidirectional"))
    )
    (net (code "67") (name "unconnected-(U3-IO19-Pad31)") (class "Default")
      (node (ref "U3") (pin "31") (pinfunction "IO19_31") (pintype "bidirectional"))
    )
    (net (code "68") (name "unconnected-(U3-IO26-Pad11)") (class "Default")
      (node (ref "U3") (pin "11") (pinfunction "IO26_11") (pintype "bidirectional"))
    )
    (net (code "69") (name "unconnected-(U3-SCL{slash}CLK-Pad20)") (class "Default")
      (node (ref "U3") (pin "20") (pinfunction "SCL/CLK_20") (pintype "bidirectional"))
    )
    (net (code "70") (name "unconnected-(U3-SCS{slash}CMD-Pad19)") (class "Default")
      (node (ref "U3") (pin "19") (pinfunction "SCS/CMD_19") (pintype "bidirectional"))
    )
    (net (code "71") (name "unconnected-(U3-SDI{slash}SD1-Pad22)") (class "Default")
      (node (ref "U3") (pin "22") (pinfunction "SDI/SD1_22") (pintype "bidirectional"))
    )
    (net (code "72") (name "unconnected-(U3-SDO{slash}SD0-Pad21)") (class "Default")
      (node (ref "U3") (pin "21") (pinfunction "SDO/SD0_21") (pintype "bidirectional"))
    )
    (net (code "73") (name "unconnected-(U3-SENSOR_VN-Pad5)") (class "Default")
      (node (ref "U3") (pin "5") (pinfunction "SENSOR_VN_5") (pintype "input"))
    )
    (net (code "74") (name "unconnected-(U3-SENSOR_VP-Pad4)") (class "Default")
      (node (ref "U3") (pin "4") (pinfunction "SENSOR_VP_4") (pintype "input"))
    )
    (net (code "75") (name "unconnected-(U3-SHD{slash}SD2-Pad17)") (class "Default")
      (node (ref "U3") (pin "17") (pinfunction "SHD/SD2_17") (pintype "bidirectional"))
    )
    (net (code "76") (name "unconnected-(U3-SWP{slash}SD3-Pad18)") (class "Default")
      (node (ref "U3") (pin "18") (pinfunction "SWP/SD3_18") (pintype "bidirectional"))
    )
  )
)
